# touch_brick.net
KiCad netlist of a schematic drawn in EAGLE
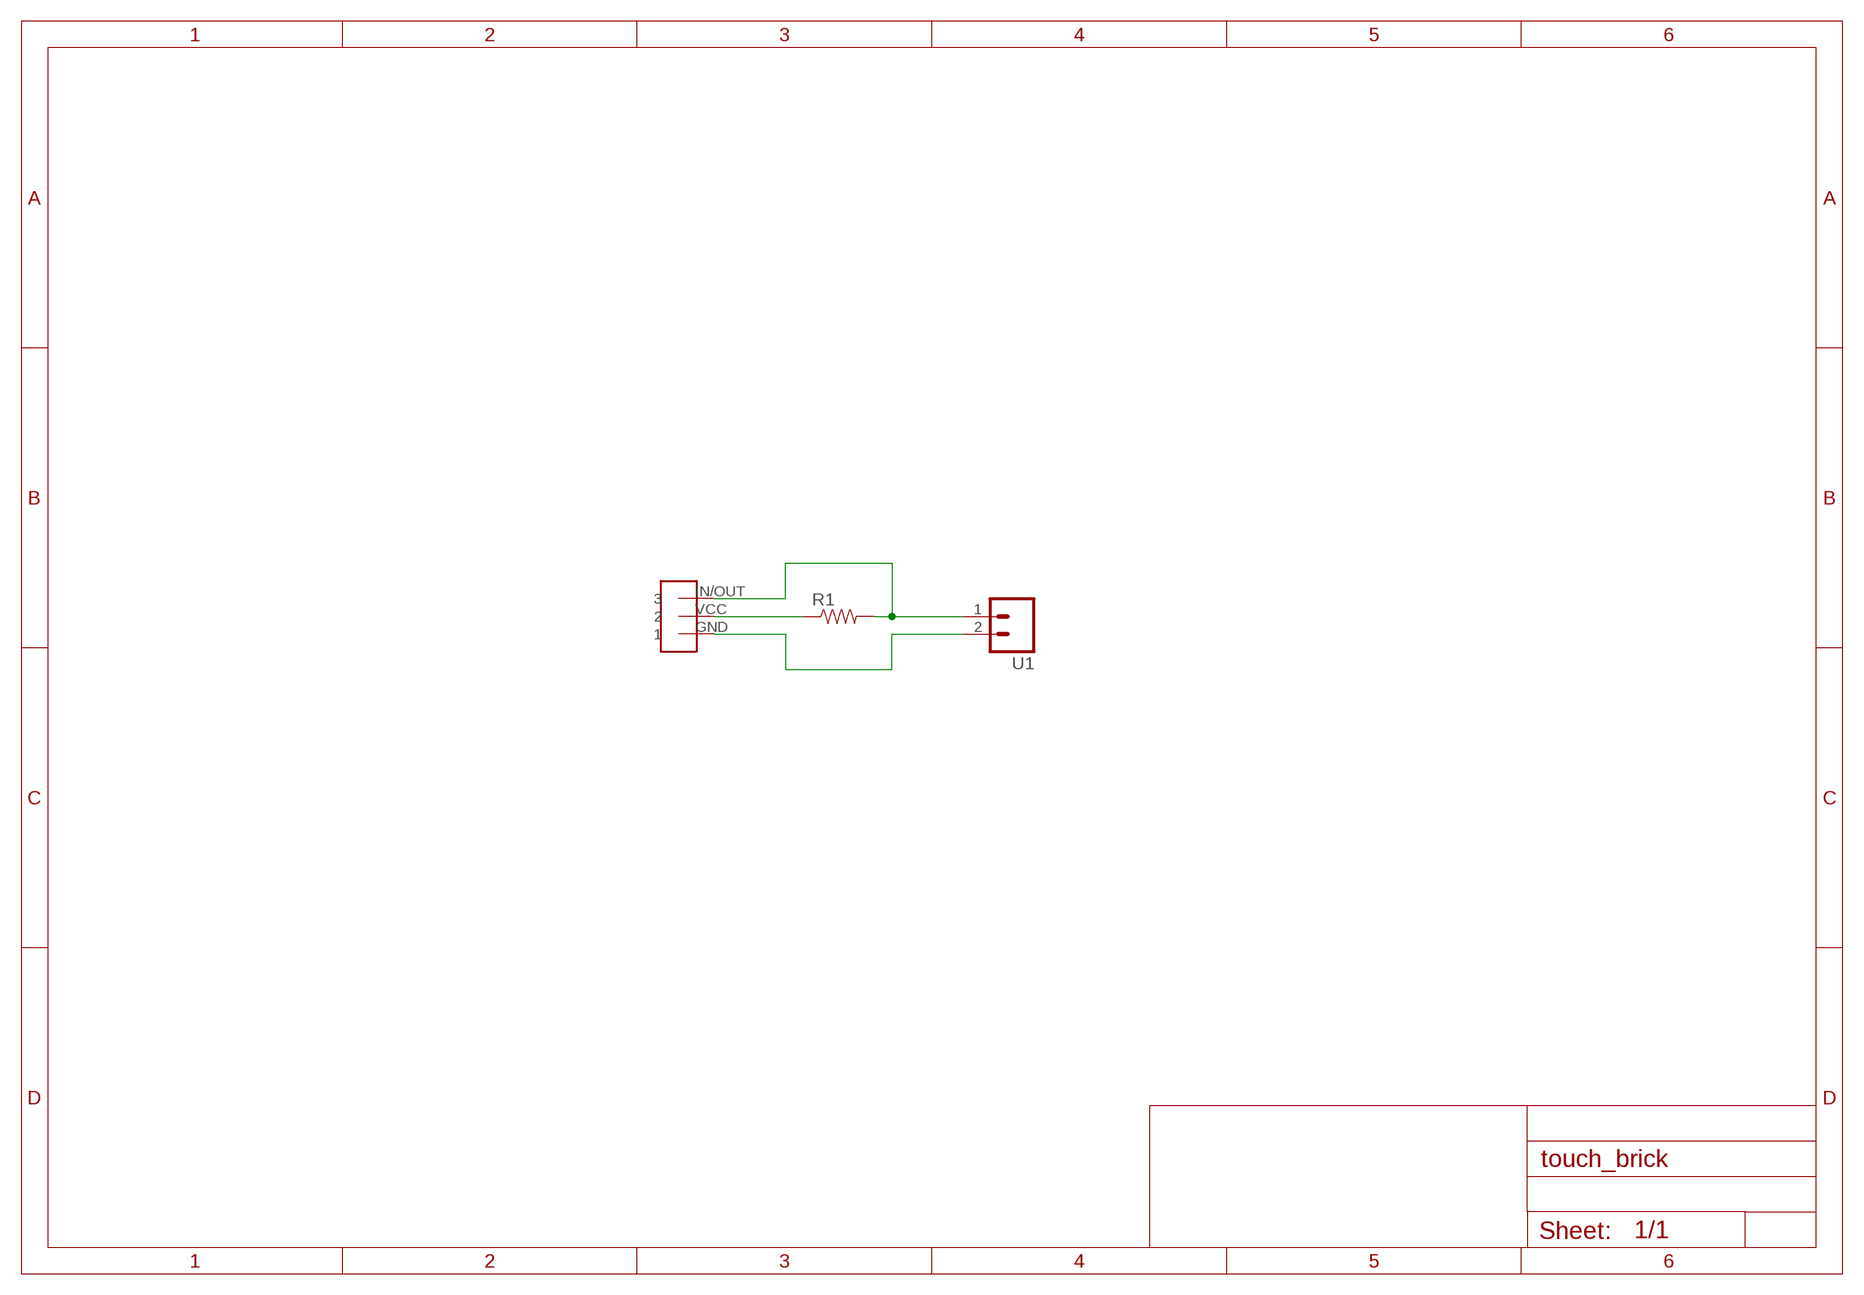
[diagram p0: schematic, sheet 1]

(export (version "E")
  (design (tool "Eeschema 10.0.6"))
  (components
    (comp (ref "R1")
      (value "RESISTORKIT")
      (footprint "eagle-import:AXIAL-0.3-KIT")
      (libsource (lib "eagle-import") (part "RESISTORKIT"))
    )
    (comp (ref "U$1")
      (value "BRICK-3PIN")
      (footprint "eagle-import:BRICK_3PIN")
      (libsource (lib "eagle-import") (part "BRICK-3PIN"))
    )
    (comp (ref "U1")
      (value "M02LOCK")
      (footprint "eagle-import:1X02_LOCK")
      (libsource (lib "eagle-import") (part "M02LOCK"))
    )
  )
  (nets
    (net (code "1") (name "Net-(R1-1)") (class "Default")
      (node (ref "R1") (pin "P$1") (pinfunction "1_P$1") (pintype "passive"))
      (node (ref "U$1") (pin "VCC") (pinfunction "2_VCC") (pintype "bidirectional"))
    )
    (net (code "2") (name "Net-(R1-2)") (class "Default")
      (node (ref "R1") (pin "P$2") (pinfunction "2_P$2") (pintype "passive"))
      (node (ref "U$1") (pin "IN/OUT") (pinfunction "3_IN/OUT") (pintype "bidirectional"))
      (node (ref "U1") (pin "1") (pinfunction "1_1") (pintype "passive"))
    )
    (net (code "3") (name "Net-(U$1-1)") (class "Default")
      (node (ref "U$1") (pin "GND") (pinfunction "1_GND") (pintype "bidirectional"))
      (node (ref "U1") (pin "2") (pinfunction "2_2") (pintype "passive"))
    )
  )
)
